# trinky.net
KiCad netlist of a schematic drawn in EAGLE
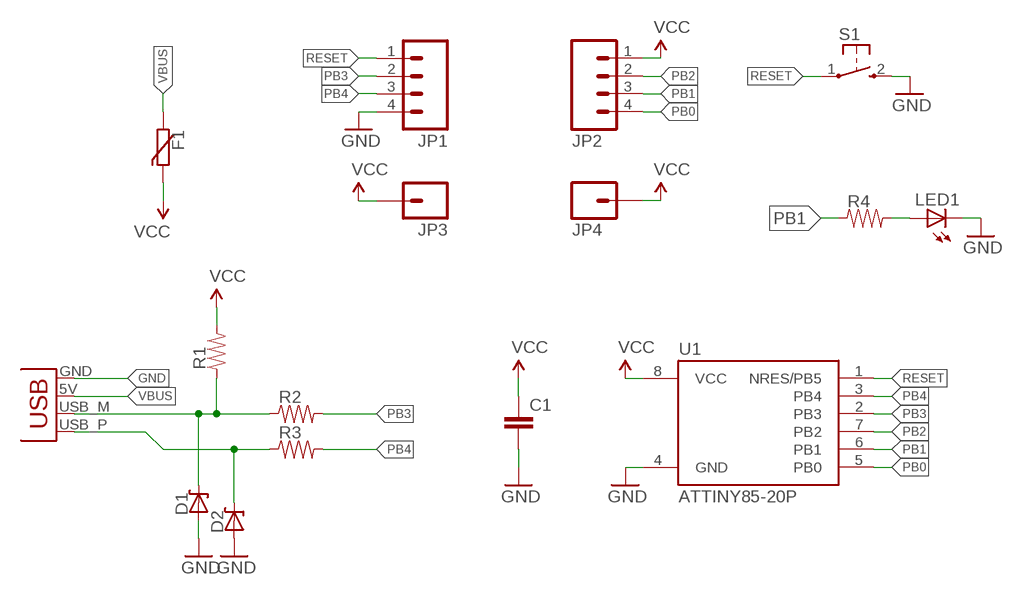
[diagram p0: schematic, sheet 1]

(export (version "E")
  (design (tool "Eeschema 10.0.6"))
  (components
    (comp (ref "C1")
      (value "CAPEZ")
      (footprint "eagle-import:CAP-PTH-SMALLEZ")
      (libsource (lib "eagle-import") (part "CAPEZ"))
    )
    (comp (ref "D1")
      (value "ZENER-DIODE-AXIAL-0.385")
      (footprint "eagle-import:SMALL-DIODE-0.385")
      (libsource (lib "eagle-import") (part "ZENER-DIODE-AXIAL-0.385"))
    )
    (comp (ref "D2")
      (value "ZENER-DIODE-AXIAL-0.3")
      (footprint "eagle-import:SMALL-DIODE-0.3")
      (libsource (lib "eagle-import") (part "ZENER-DIODE-AXIAL-0.3"))
    )
    (comp (ref "F1")
      (value "1812-RESETABLE-POLYFUSE")
      (footprint "eagle-import:1812-PTC-POLYFUSE")
      (libsource (lib "eagle-import") (part "1812-RESETABLE-POLYFUSE"))
    )
    (comp (ref "JP1")
      (value "M04LONGPADS")
      (footprint "eagle-import:1X04_LONGPADS")
      (libsource (lib "eagle-import") (part "M04LONGPADS"))
    )
    (comp (ref "JP2")
      (value "M04LONGPADS")
      (footprint "eagle-import:1X04_LONGPADS")
      (libsource (lib "eagle-import") (part "M04LONGPADS"))
    )
    (comp (ref "JP3")
      (value "M01PTH_LONGPAD")
      (footprint "eagle-import:1X01_LONGPAD")
      (libsource (lib "eagle-import") (part "M01PTH_LONGPAD"))
    )
    (comp (ref "JP4")
      (value "M01PTH_LONGPAD")
      (footprint "eagle-import:1X01_LONGPAD")
      (libsource (lib "eagle-import") (part "M01PTH_LONGPAD"))
    )
    (comp (ref "JP5")
      (value "USBPCB")
      (footprint "eagle-import:USB-A-PCB")
      (libsource (lib "eagle-import") (part "USBPCB"))
    )
    (comp (ref "LED1")
      (value "LED3MM")
      (footprint "eagle-import:LED3MM")
      (libsource (lib "eagle-import") (part "LED3MM"))
    )
    (comp (ref "R1")
      (value "RESISTOR-AXIAL-0.2")
      (footprint "eagle-import:AXIAL-0.2")
      (libsource (lib "eagle-import") (part "RESISTOR-AXIAL-0.2"))
    )
    (comp (ref "R2")
      (value "RESISTOR-AXIAL-0.4")
      (footprint "eagle-import:AXIAL-0.4")
      (libsource (lib "eagle-import") (part "RESISTOR-AXIAL-0.4"))
    )
    (comp (ref "R3")
      (value "RESISTOR-AXIAL-0.4")
      (footprint "eagle-import:AXIAL-0.4")
      (libsource (lib "eagle-import") (part "RESISTOR-AXIAL-0.4"))
    )
    (comp (ref "R4")
      (value "RESISTOR-AXIAL-0.3")
      (footprint "eagle-import:AXIAL-0.3")
      (libsource (lib "eagle-import") (part "RESISTOR-AXIAL-0.3"))
    )
    (comp (ref "S1")
      (value "TACTILE-SWITCH-2PINS-REMOVED")
      (footprint "eagle-import:BUTTON-2PINS-REMOVED")
      (libsource (lib "eagle-import") (part "TACTILE-SWITCH-2PINS-REMOVED"))
    )
    (comp (ref "U1")
      (value "ATTINY85-20P")
      (footprint "eagle-import:PDIP08_300MIL")
      (libsource (lib "eagle-import") (part "ATTINY85P-20"))
    )
  )
  (nets
    (net (code "1") (name "GND") (class "Default")
      (node (ref "C1") (pin "2") (pinfunction "2_2") (pintype "passive"))
      (node (ref "D1") (pin "P$1") (pinfunction "P$1_P$1") (pintype "bidirectional"))
      (node (ref "D2") (pin "P$1") (pinfunction "P$1_P$1") (pintype "bidirectional"))
      (node (ref "JP1") (pin "4") (pinfunction "4_4") (pintype "passive"))
      (node (ref "JP5") (pin "GND") (pinfunction "GND_GND") (pintype "bidirectional"))
      (node (ref "LED1") (pin "K") (pinfunction "C_K") (pintype "passive"))
      (node (ref "S1") (pin "2") (pinfunction "2_2") (pintype "passive"))
      (node (ref "U1") (pin "4") (pinfunction "GND_4") (pintype "power_in"))
    )
    (net (code "2") (name "Net-(JP5-D+)") (class "Default")
      (node (ref "D2") (pin "P$2") (pinfunction "P$2_P$2") (pintype "bidirectional"))
      (node (ref "JP5") (pin "USB_P") (pinfunction "D+_USB_P") (pintype "bidirectional"))
      (node (ref "R3") (pin "P$1") (pinfunction "P$1_P$1") (pintype "bidirectional"))
    )
    (net (code "3") (name "Net-(JP5-D-)") (class "Default")
      (node (ref "D1") (pin "P$2") (pinfunction "P$2_P$2") (pintype "bidirectional"))
      (node (ref "JP5") (pin "USB_M") (pinfunction "D-_USB_M") (pintype "bidirectional"))
      (node (ref "R1") (pin "P$1") (pinfunction "P$1_P$1") (pintype "bidirectional"))
      (node (ref "R2") (pin "P$1") (pinfunction "P$1_P$1") (pintype "bidirectional"))
    )
    (net (code "4") (name "Net-(LED1-PadA)") (class "Default")
      (node (ref "LED1") (pin "A") (pinfunction "A_A") (pintype "passive"))
      (node (ref "R4") (pin "P$2") (pinfunction "P$2_P$2") (pintype "bidirectional"))
    )
    (net (code "5") (name "PB0") (class "Default")
      (node (ref "JP2") (pin "4") (pinfunction "4_4") (pintype "passive"))
      (node (ref "U1") (pin "5") (pinfunction "PB0_5") (pintype "bidirectional"))
    )
    (net (code "6") (name "PB1") (class "Default")
      (node (ref "JP2") (pin "3") (pinfunction "3_3") (pintype "passive"))
      (node (ref "R4") (pin "P$1") (pinfunction "P$1_P$1") (pintype "bidirectional"))
      (node (ref "U1") (pin "6") (pinfunction "PB1_6") (pintype "bidirectional"))
    )
    (net (code "7") (name "PB2") (class "Default")
      (node (ref "JP2") (pin "2") (pinfunction "2_2") (pintype "passive"))
      (node (ref "U1") (pin "7") (pinfunction "PB2_7") (pintype "bidirectional"))
    )
    (net (code "8") (name "PB3") (class "Default")
      (node (ref "JP1") (pin "2") (pinfunction "2_2") (pintype "passive"))
      (node (ref "R2") (pin "P$2") (pinfunction "P$2_P$2") (pintype "bidirectional"))
      (node (ref "U1") (pin "2") (pinfunction "PB3_2") (pintype "bidirectional"))
    )
    (net (code "9") (name "PB4") (class "Default")
      (node (ref "JP1") (pin "3") (pinfunction "3_3") (pintype "passive"))
      (node (ref "R3") (pin "P$2") (pinfunction "P$2_P$2") (pintype "bidirectional"))
      (node (ref "U1") (pin "3") (pinfunction "PB4_3") (pintype "bidirectional"))
    )
    (net (code "10") (name "RESET") (class "Default")
      (node (ref "JP1") (pin "1") (pinfunction "1_1") (pintype "passive"))
      (node (ref "S1") (pin "1") (pinfunction "1_1") (pintype "passive"))
      (node (ref "U1") (pin "1") (pinfunction "NRES/PB5_1") (pintype "bidirectional"))
    )
    (net (code "11") (name "VBUS") (class "Default")
      (node (ref "F1") (pin "P$1") (pinfunction "P$1_P$1") (pintype "bidirectional"))
      (node (ref "JP5") (pin "5V") (pinfunction "VBUS_5V") (pintype "bidirectional"))
    )
    (net (code "12") (name "VCC") (class "Default")
      (node (ref "C1") (pin "1") (pinfunction "1_1") (pintype "passive"))
      (node (ref "F1") (pin "P$2") (pinfunction "P$2_P$2") (pintype "bidirectional"))
      (node (ref "JP2") (pin "1") (pinfunction "1_1") (pintype "passive"))
      (node (ref "JP3") (pin "1") (pinfunction "1_1") (pintype "passive"))
      (node (ref "JP4") (pin "1") (pinfunction "1_1") (pintype "passive"))
      (node (ref "R1") (pin "P$2") (pinfunction "P$2_P$2") (pintype "bidirectional"))
      (node (ref "U1") (pin "8") (pinfunction "VCC_8") (pintype "power_in"))
    )
  )
)
